# main_microusb.net
KiCad netlist of a schematic drawn in Altium Designer
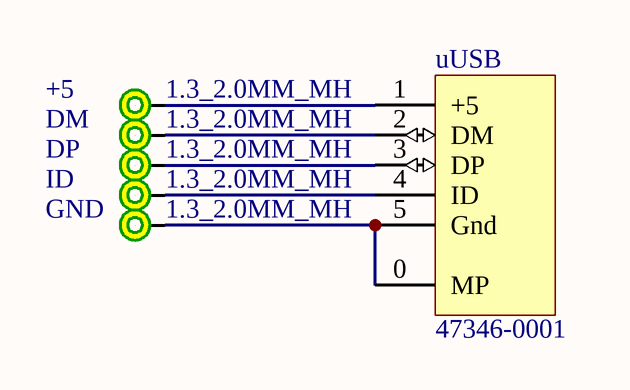
[diagram p0: main_microusb.SchDoc]

(export (version "E")
  (design (tool "Eeschema 10.0.6"))
  (components
    (comp (ref "+5")
      (value "1.3_2.0MM_MH")
      (footprint "1.3_2.0MM_PH")
      (fields
        (field (name "PART NUMBER") "PCB_0092")
        (field (name "MANUFACTURER") "Misc PCB")
        (field (name "MANUFACTURER PART NUMBER") "S46")
        (field (name "PUBLISHER") "shawn@shaolo.com")
        (field (name "REVIEWER") "shawn@shaolo.com")
      )
      (libsource (lib "Altium Access") (part "Plated Hole"))
    )
    (comp (ref "DM")
      (value "1.3_2.0MM_MH")
      (footprint "1.3_2.0MM_PH")
      (fields
        (field (name "PART NUMBER") "PCB_0092")
        (field (name "MANUFACTURER") "Misc PCB")
        (field (name "MANUFACTURER PART NUMBER") "S46")
        (field (name "PUBLISHER") "shawn@shaolo.com")
        (field (name "REVIEWER") "shawn@shaolo.com")
      )
      (libsource (lib "Altium Access") (part "Plated Hole"))
    )
    (comp (ref "DP")
      (value "1.3_2.0MM_MH")
      (footprint "1.3_2.0MM_PH")
      (fields
        (field (name "PART NUMBER") "PCB_0092")
        (field (name "MANUFACTURER") "Misc PCB")
        (field (name "MANUFACTURER PART NUMBER") "S46")
        (field (name "PUBLISHER") "shawn@shaolo.com")
        (field (name "REVIEWER") "shawn@shaolo.com")
      )
      (libsource (lib "Altium Access") (part "Plated Hole"))
    )
    (comp (ref "GND")
      (value "1.3_2.0MM_MH")
      (footprint "1.3_2.0MM_PH")
      (fields
        (field (name "PART NUMBER") "PCB_0092")
        (field (name "MANUFACTURER") "Misc PCB")
        (field (name "MANUFACTURER PART NUMBER") "S46")
        (field (name "PUBLISHER") "shawn@shaolo.com")
        (field (name "REVIEWER") "shawn@shaolo.com")
      )
      (libsource (lib "Altium Access") (part "Plated Hole"))
    )
    (comp (ref "ID")
      (value "1.3_2.0MM_MH")
      (footprint "1.3_2.0MM_PH")
      (fields
        (field (name "PART NUMBER") "PCB_0092")
        (field (name "MANUFACTURER") "Misc PCB")
        (field (name "MANUFACTURER PART NUMBER") "S46")
        (field (name "PUBLISHER") "shawn@shaolo.com")
        (field (name "REVIEWER") "shawn@shaolo.com")
      )
      (libsource (lib "Altium Access") (part "Plated Hole"))
    )
    (comp (ref "uUSB")
      (value "47346-0001")
      (footprint "USB Micro B")
      (description "CONN RCPT 5POS MICRO USB R/A")
      (fields
        (field (name "PART NUMBER") "CONN_0056")
        (field (name "MANUFACTURER") "Molex")
        (field (name "PUBLISHER") "shawn@shaolo.com")
        (field (name "REVIEWER") "shawn@shaolo.com")
      )
      (libsource (lib "Altium Access") (part "USB_MINI"))
    )
  )
  (nets
    (net (code "1") (name "Net-(uUSB-+5)") (class "Default")
      (node (ref "+5") (pin "1") (pinfunction "1_1") (pintype "passive"))
      (node (ref "uUSB") (pin "1") (pinfunction "+5_1") (pintype "power_in"))
    )
    (net (code "2") (name "Net-(uUSB-DM)") (class "Default")
      (node (ref "DM") (pin "1") (pinfunction "1_1") (pintype "passive"))
      (node (ref "uUSB") (pin "2") (pinfunction "DM_2") (pintype "bidirectional"))
    )
    (net (code "3") (name "Net-(uUSB-DP)") (class "Default")
      (node (ref "DP") (pin "1") (pinfunction "1_1") (pintype "passive"))
      (node (ref "uUSB") (pin "3") (pinfunction "DP_3") (pintype "bidirectional"))
    )
    (net (code "4") (name "Net-(uUSB-Gnd)") (class "Default")
      (node (ref "GND") (pin "1") (pinfunction "1_1") (pintype "passive"))
      (node (ref "uUSB") (pin "0") (pinfunction "MP_0") (pintype "passive"))
      (node (ref "uUSB") (pin "5") (pinfunction "Gnd_5") (pintype "power_in"))
    )
    (net (code "5") (name "Net-(uUSB-ID)") (class "Default")
      (node (ref "ID") (pin "1") (pinfunction "1_1") (pintype "passive"))
      (node (ref "uUSB") (pin "4") (pinfunction "ID_4") (pintype "passive"))
    )
  )
)
